# 3.net
KiCad netlist of a schematic drawn in EasyEDA
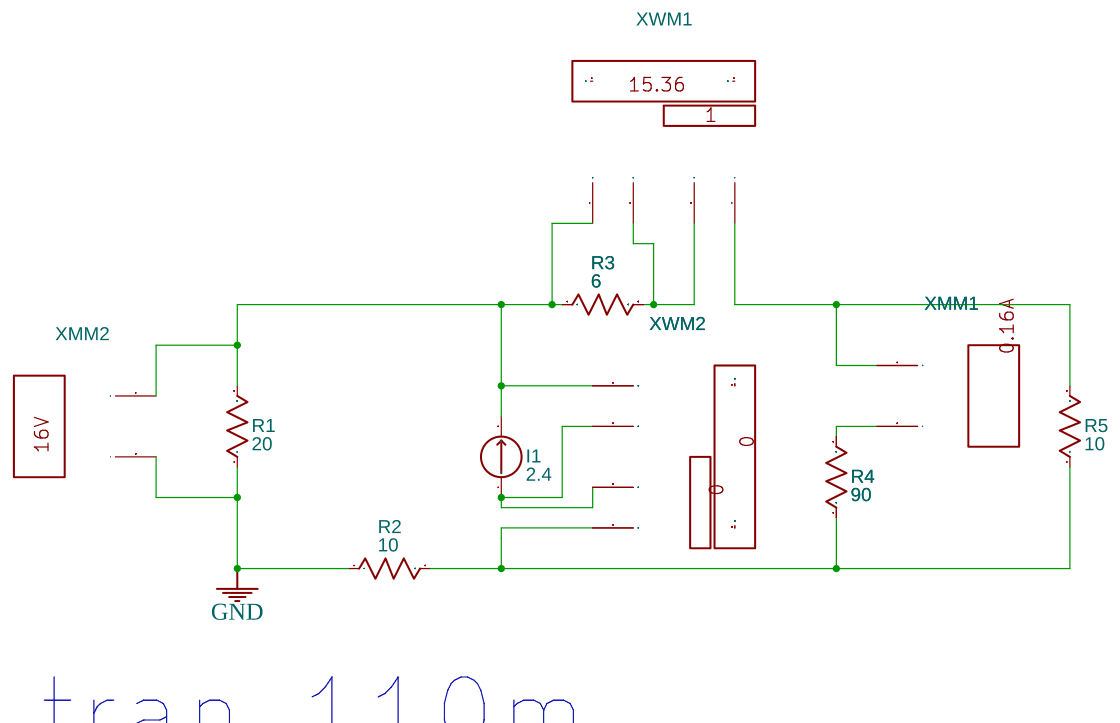
[diagram p0: schematic sheet]

(export (version "E")
  (design (tool "Eeschema 10.0.6"))
  (components
    (comp (ref "I1") (value "2.4") (libsource (lib "") (part "IDC")))
    (comp (ref "R1") (value "20") (libsource (lib "") (part "Resistor_US_1")))
    (comp (ref "R2") (value "10") (libsource (lib "") (part "Resistor_US")))
    (comp (ref "R3") (value "6") (libsource (lib "") (part "Resistor_US")))
    (comp (ref "R4") (value "90") (libsource (lib "") (part "Resistor_US_1")))
    (comp (ref "R5") (value "10") (libsource (lib "") (part "Resistor_US_1")))
    (comp (ref "XMM1") (value "Multimeter") (libsource (lib "") (part "MULTIMETER_1")))
    (comp (ref "XMM2") (value "Multimeter") (libsource (lib "") (part "MULTIMETER")))
    (comp (ref "XWM1") (value "Wattmeter") (libsource (lib "") (part "WATTMETER_1")))
    (comp (ref "XWM2") (value "Wattmeter") (libsource (lib "") (part "WATTMETER")))
  )
  (nets
    (net (code "1") (name "GND") (class "Default")
      (node (ref "R1") (pin "1") (pinfunction "1_1") (pintype "unspecified"))
      (node (ref "R2") (pin "1") (pinfunction "1_1") (pintype "unspecified"))
      (node (ref "XMM2") (pin "2") (pinfunction "I_2") (pintype "unspecified"))
    )
    (net (code "2") (name "Net-(XMM1-+)") (class "Default")
      (node (ref "R5") (pin "2") (pinfunction "2_2") (pintype "unspecified"))
      (node (ref "XMM1") (pin "1") (pinfunction "+_1") (pintype "unspecified"))
      (node (ref "XWM1") (pin "4") (pinfunction "I-_4") (pintype "unspecified"))
    )
    (net (code "3") (name "Net-(XMM1-I)") (class "Default")
      (node (ref "R4") (pin "2") (pinfunction "2_2") (pintype "unspecified"))
      (node (ref "XMM1") (pin "2") (pinfunction "I_2") (pintype "unspecified"))
    )
    (net (code "4") (name "Net-(XMM2-+)") (class "Default")
      (node (ref "I1") (pin "2") (pinfunction "2_2") (pintype "unspecified"))
      (node (ref "R1") (pin "2") (pinfunction "2_2") (pintype "unspecified"))
      (node (ref "R3") (pin "1") (pinfunction "1_1") (pintype "unspecified"))
      (node (ref "XMM2") (pin "1") (pinfunction "+_1") (pintype "unspecified"))
      (node (ref "XWM1") (pin "1") (pinfunction "V+_1") (pintype "unspecified"))
      (node (ref "XWM2") (pin "1") (pinfunction "V+_1") (pintype "unspecified"))
    )
    (net (code "5") (name "Net-(XWM1-I+)") (class "Default")
      (node (ref "R3") (pin "2") (pinfunction "2_2") (pintype "unspecified"))
      (node (ref "XWM1") (pin "2") (pinfunction "V-_2") (pintype "unspecified"))
      (node (ref "XWM1") (pin "3") (pinfunction "I+_3") (pintype "unspecified"))
    )
    (net (code "6") (name "Net-(XWM2-I+)") (class "Default")
      (node (ref "I1") (pin "1") (pinfunction "1_1") (pintype "unspecified"))
      (node (ref "XWM2") (pin "2") (pinfunction "V-_2") (pintype "unspecified"))
      (node (ref "XWM2") (pin "3") (pinfunction "I+_3") (pintype "unspecified"))
    )
    (net (code "7") (name "Net-(XWM2-I-)") (class "Default")
      (node (ref "R2") (pin "2") (pinfunction "2_2") (pintype "unspecified"))
      (node (ref "R4") (pin "1") (pinfunction "1_1") (pintype "unspecified"))
      (node (ref "R5") (pin "1") (pinfunction "1_1") (pintype "unspecified"))
      (node (ref "XWM2") (pin "4") (pinfunction "I-_4") (pintype "unspecified"))
    )
    (net (code "8") (name "unconnected-(XWM1-PadP)") (class "Default")
      (node (ref "XWM1") (pin "P") (pinfunction "P_P") (pintype "unspecified"))
    )
    (net (code "9") (name "unconnected-(XWM1-PadPF)") (class "Default")
      (node (ref "XWM1") (pin "PF") (pinfunction "PF_PF") (pintype "unspecified"))
    )
    (net (code "10") (name "unconnected-(XWM2-PadP)") (class "Default")
      (node (ref "XWM2") (pin "P") (pinfunction "P_P") (pintype "unspecified"))
    )
    (net (code "11") (name "unconnected-(XWM2-PadPF)") (class "Default")
      (node (ref "XWM2") (pin "PF") (pinfunction "PF_PF") (pintype "unspecified"))
    )
  )
)
